# SparkFun_TMC6300_Breakout.net
KiCad netlist of a schematic drawn in EAGLE
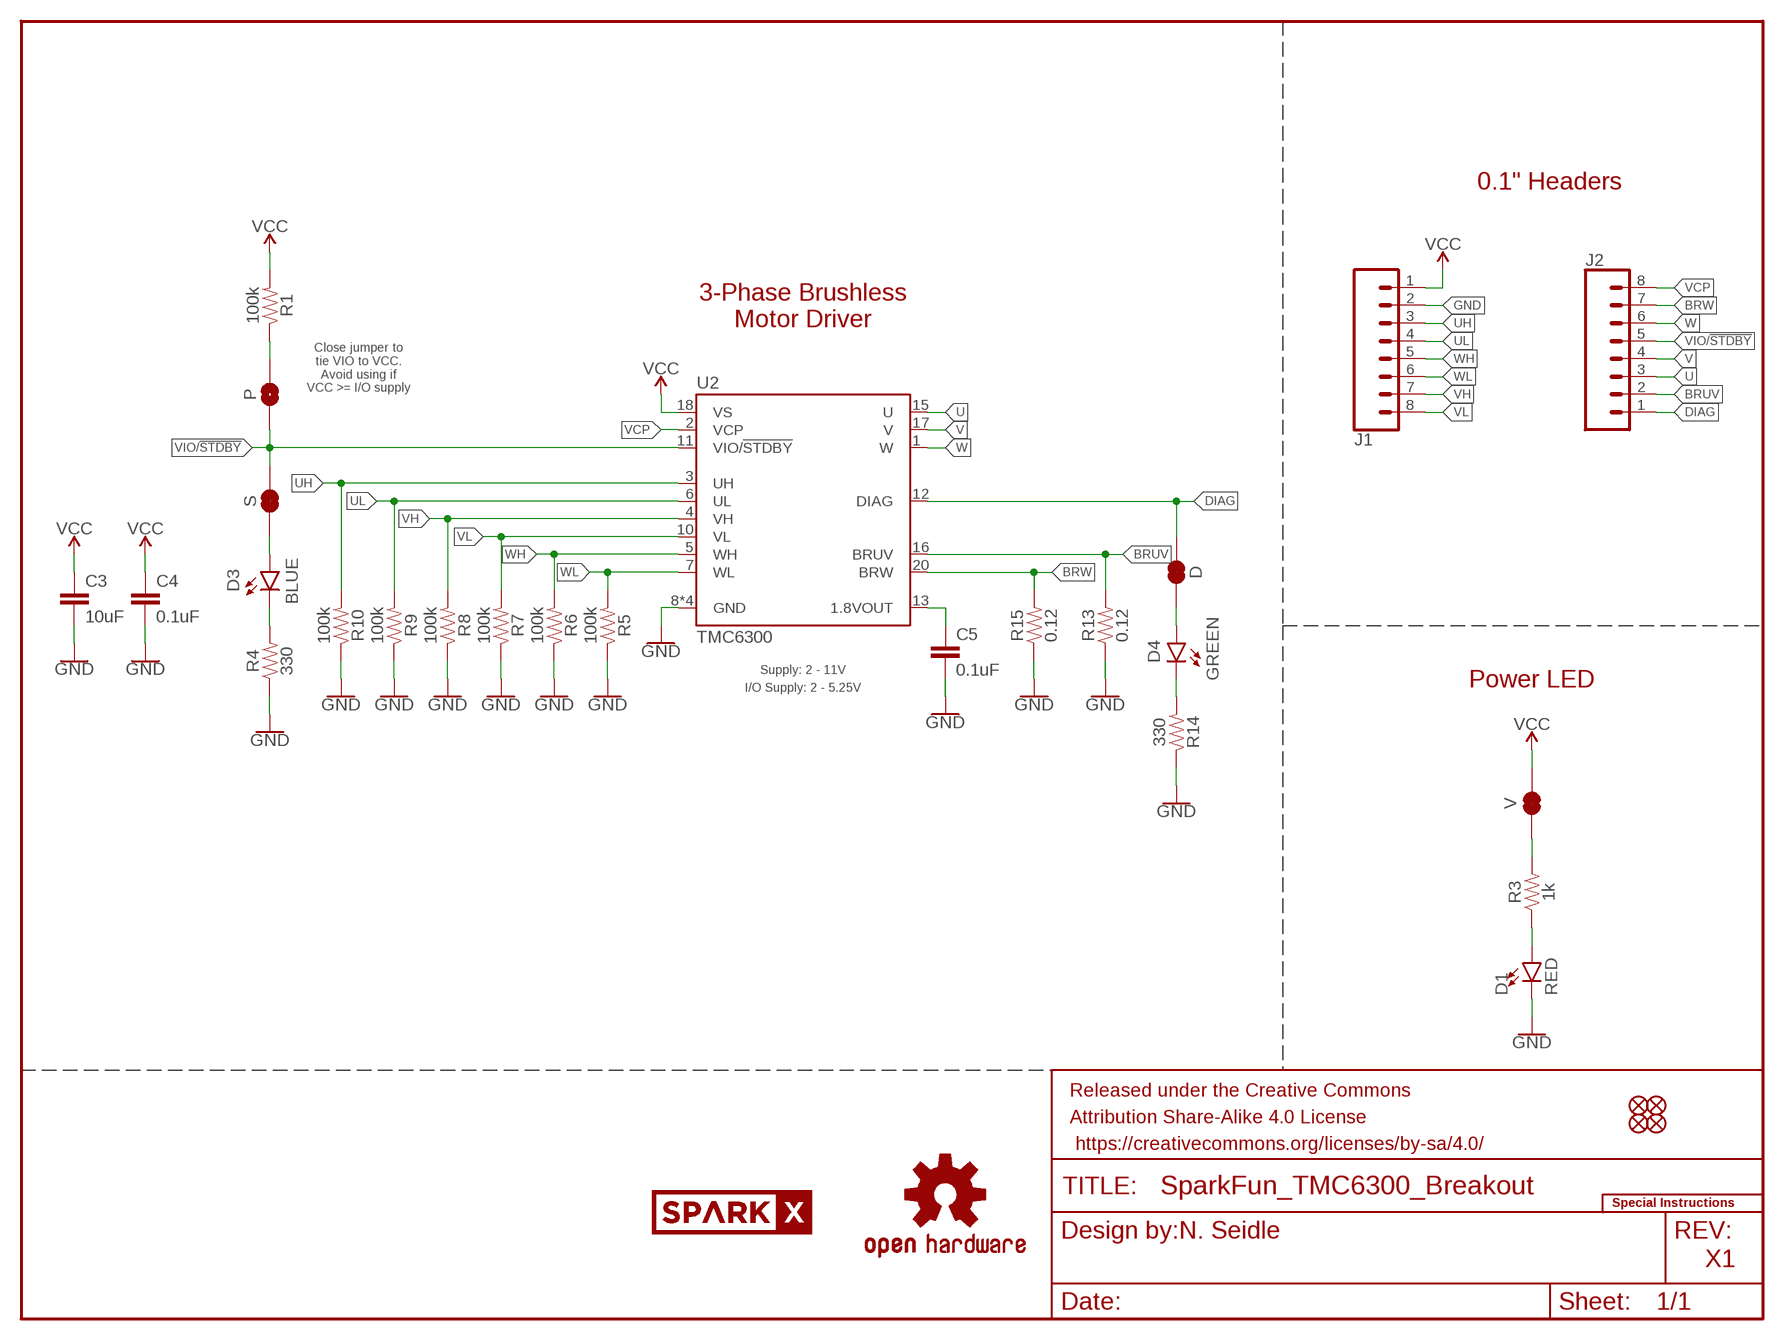
[diagram p0: schematic, sheet 1]

(export (version "E")
  (design (tool "Eeschema 10.0.6"))
  (components
    (comp (ref "C3")
      (value "10uF")
      (footprint "eagle-import:0805")
      (libsource (lib "eagle-import") (part "10UF-0805-25V-10%"))
    )
    (comp (ref "C4")
      (value "0.1uF")
      (footprint "eagle-import:0603")
      (libsource (lib "eagle-import") (part "0.1UF-0603-25V-10%-X7R-WE"))
    )
    (comp (ref "C5")
      (value "0.1uF")
      (footprint "eagle-import:0603")
      (libsource (lib "eagle-import") (part "0.1UF-0603-25V-10%-X7R-WE"))
    )
    (comp (ref "D")
      (value "JUMPER-SMT_2_NC_TRACE_SILK")
      (footprint "eagle-import:SMT-JUMPER_2_NC_TRACE_SILK")
      (libsource (lib "eagle-import") (part "JUMPER-SMT_2_NC_TRACE_SILK"))
    )
    (comp (ref "D1")
      (value "RED")
      (footprint "eagle-import:LED-0603")
      (libsource (lib "eagle-import") (part "LED-RED0603"))
    )
    (comp (ref "D3")
      (value "BLUE")
      (footprint "eagle-import:LED-0603")
      (libsource (lib "eagle-import") (part "LED-BLUE0603"))
    )
    (comp (ref "D4")
      (value "GREEN")
      (footprint "eagle-import:LED-0603")
      (libsource (lib "eagle-import") (part "LED-GREEN0603"))
    )
    (comp (ref "FD1")
      (value "FIDUCIALUFIDUCIAL")
      (footprint "eagle-import:FIDUCIAL-MICRO")
      (libsource (lib "eagle-import") (part "FIDUCIALUFIDUCIAL"))
    )
    (comp (ref "FD2")
      (value "FIDUCIALUFIDUCIAL")
      (footprint "eagle-import:FIDUCIAL-MICRO")
      (libsource (lib "eagle-import") (part "FIDUCIALUFIDUCIAL"))
    )
    (comp (ref "FD3")
      (value "FIDUCIALUFIDUCIAL")
      (footprint "eagle-import:FIDUCIAL-MICRO")
      (libsource (lib "eagle-import") (part "FIDUCIALUFIDUCIAL"))
    )
    (comp (ref "FD4")
      (value "FIDUCIALUFIDUCIAL")
      (footprint "eagle-import:FIDUCIAL-MICRO")
      (libsource (lib "eagle-import") (part "FIDUCIALUFIDUCIAL"))
    )
    (comp (ref "FRAME1")
      (value "FRAME-LETTER")
      (footprint "eagle-import:CREATIVE_COMMONS")
      (fields (field (name "DESIGNER") "Ricardo Ramos"))
      (libsource (lib "eagle-import") (part "FRAME-LETTER"))
    )
    (comp (ref "J1")
      (value "CONN_08LOCK_NO_SILK")
      (footprint "eagle-import:1X08_LOCK_NO_SILK")
      (libsource (lib "eagle-import") (part "CONN_08LOCK_NO_SILK"))
    )
    (comp (ref "J2")
      (value "CONN_08LOCK_NO_SILK")
      (footprint "eagle-import:1X08_LOCK_NO_SILK")
      (libsource (lib "eagle-import") (part "CONN_08LOCK_NO_SILK"))
    )
    (comp (ref "LOGO1")
      (value "OSHW-LOGONO_SILK")
      (footprint "eagle-import:DUMMY")
      (libsource (lib "eagle-import") (part "OSHW-LOGONO_SILK"))
    )
    (comp (ref "LOGO2")
      (value "SPECIAL_INSTRUCTIONS-ORDERING")
      (footprint "eagle-import:ORDERING_INSTRUCTIONS")
      (libsource (lib "eagle-import") (part "SPECIAL_INSTRUCTIONS-ORDERING"))
    )
    (comp (ref "P")
      (value "JUMPER-SMT_2_NO_SILK")
      (footprint "eagle-import:SMT-JUMPER_2_NO_SILK")
      (libsource (lib "eagle-import") (part "JUMPER-SMT_2_NO_SILK"))
    )
    (comp (ref "R1")
      (value "100k")
      (footprint "eagle-import:0603")
      (libsource (lib "eagle-import") (part "100KOHM-0603-1/10W-1%"))
    )
    (comp (ref "R3")
      (value "1k")
      (footprint "eagle-import:0603")
      (libsource (lib "eagle-import") (part "1KOHM-0603-1/10W-1%"))
    )
    (comp (ref "R4")
      (value "330")
      (footprint "eagle-import:0603")
      (libsource (lib "eagle-import") (part "330OHM-0603-1/10W-1%"))
    )
    (comp (ref "R5")
      (value "100k")
      (footprint "eagle-import:0603")
      (libsource (lib "eagle-import") (part "100KOHM-0603-1/10W-1%"))
    )
    (comp (ref "R6")
      (value "100k")
      (footprint "eagle-import:0603")
      (libsource (lib "eagle-import") (part "100KOHM-0603-1/10W-1%"))
    )
    (comp (ref "R7")
      (value "100k")
      (footprint "eagle-import:0603")
      (libsource (lib "eagle-import") (part "100KOHM-0603-1/10W-1%"))
    )
    (comp (ref "R8")
      (value "100k")
      (footprint "eagle-import:0603")
      (libsource (lib "eagle-import") (part "100KOHM-0603-1/10W-1%"))
    )
    (comp (ref "R9")
      (value "100k")
      (footprint "eagle-import:0603")
      (libsource (lib "eagle-import") (part "100KOHM-0603-1/10W-1%"))
    )
    (comp (ref "R10")
      (value "100k")
      (footprint "eagle-import:0603")
      (libsource (lib "eagle-import") (part "100KOHM-0603-1/10W-1%"))
    )
    (comp (ref "R13")
      (value "0.12")
      (footprint "eagle-import:1206")
      (libsource (lib "eagle-import") (part "0.12OHM-1206-1/2W-1%"))
    )
    (comp (ref "R14")
      (value "330")
      (footprint "eagle-import:0603")
      (libsource (lib "eagle-import") (part "330OHM-0603-1/10W-1%"))
    )
    (comp (ref "R15")
      (value "0.12")
      (footprint "eagle-import:1206")
      (libsource (lib "eagle-import") (part "0.12OHM-1206-1/2W-1%"))
    )
    (comp (ref "S")
      (value "JUMPER-SMT_2_NC_TRACE_SILK")
      (footprint "eagle-import:SMT-JUMPER_2_NC_TRACE_SILK")
      (libsource (lib "eagle-import") (part "JUMPER-SMT_2_NC_TRACE_SILK"))
    )
    (comp (ref "U$36")
      (value "SPARKX-LOGO2")
      (footprint "eagle-import:SPARKX-TINY")
      (libsource (lib "eagle-import") (part "SPARKX-LOGO2"))
    )
    (comp (ref "U$37")
      (value "SPARKX-LOGO2")
      (footprint "eagle-import:SPARKX-TINY")
      (libsource (lib "eagle-import") (part "SPARKX-LOGO2"))
    )
    (comp (ref "U2")
      (value "TMC6300")
      (footprint "eagle-import:QFN-20")
      (libsource (lib "eagle-import") (part "TMC6300"))
    )
    (comp (ref "V")
      (value "JUMPER-SMT_2_NC_TRACE_SILK")
      (footprint "eagle-import:SMT-JUMPER_2_NC_TRACE_SILK")
      (libsource (lib "eagle-import") (part "JUMPER-SMT_2_NC_TRACE_SILK"))
    )
  )
  (nets
    (net (code "1") (name "/VIO{slash}~{STDBY}") (class "Default")
      (node (ref "J2") (pin "5") (pinfunction "5_5") (pintype "passive"))
      (node (ref "P") (pin "1") (pinfunction "1_1") (pintype "passive"))
      (node (ref "S") (pin "2") (pinfunction "2_2") (pintype "passive"))
      (node (ref "U2") (pin "11") (pinfunction "VIO/~{STDBY}_11") (pintype "bidirectional"))
    )
    (net (code "2") (name "BRUV") (class "Default")
      (node (ref "J2") (pin "2") (pinfunction "2_2") (pintype "passive"))
      (node (ref "R13") (pin "2") (pinfunction "2_2") (pintype "passive"))
      (node (ref "U2") (pin "16") (pinfunction "BRUV_16") (pintype "bidirectional"))
    )
    (net (code "3") (name "BRW") (class "Default")
      (node (ref "J2") (pin "7") (pinfunction "7_7") (pintype "passive"))
      (node (ref "R15") (pin "2") (pinfunction "2_2") (pintype "passive"))
      (node (ref "U2") (pin "20") (pinfunction "BRW_20") (pintype "bidirectional"))
    )
    (net (code "4") (name "DIAG") (class "Default")
      (node (ref "D") (pin "2") (pinfunction "2_2") (pintype "passive"))
      (node (ref "J2") (pin "1") (pinfunction "1_1") (pintype "passive"))
      (node (ref "U2") (pin "12") (pinfunction "DIAG_12") (pintype "bidirectional"))
    )
    (net (code "5") (name "GND") (class "Default")
      (node (ref "C3") (pin "2") (pinfunction "2_2") (pintype "passive"))
      (node (ref "C4") (pin "2") (pinfunction "2_2") (pintype "passive"))
      (node (ref "C5") (pin "2") (pinfunction "2_2") (pintype "passive"))
      (node (ref "D1") (pin "C") (pinfunction "C_C") (pintype "passive"))
      (node (ref "J1") (pin "2") (pinfunction "2_2") (pintype "passive"))
      (node (ref "R10") (pin "1") (pinfunction "1_1") (pintype "passive"))
      (node (ref "R13") (pin "1") (pinfunction "1_1") (pintype "passive"))
      (node (ref "R14") (pin "1") (pinfunction "1_1") (pintype "passive"))
      (node (ref "R15") (pin "1") (pinfunction "1_1") (pintype "passive"))
      (node (ref "R4") (pin "1") (pinfunction "1_1") (pintype "passive"))
      (node (ref "R5") (pin "1") (pinfunction "1_1") (pintype "passive"))
      (node (ref "R6") (pin "1") (pinfunction "1_1") (pintype "passive"))
      (node (ref "R7") (pin "1") (pinfunction "1_1") (pintype "passive"))
      (node (ref "R8") (pin "1") (pinfunction "1_1") (pintype "passive"))
      (node (ref "R9") (pin "1") (pinfunction "1_1") (pintype "passive"))
      (node (ref "U2") (pin "14") (pinfunction "GND_14") (pintype "bidirectional"))
      (node (ref "U2") (pin "8") (pinfunction "GND_8") (pintype "bidirectional"))
      (node (ref "U2") (pin "9") (pinfunction "GND_9") (pintype "bidirectional"))
      (node (ref "U2") (pin "PAD") (pinfunction "GND_PAD") (pintype "bidirectional"))
    )
    (net (code "6") (name "Net-(D-Pad1)") (class "Default")
      (node (ref "D") (pin "1") (pinfunction "1_1") (pintype "passive"))
      (node (ref "D4") (pin "A") (pinfunction "A_A") (pintype "passive"))
    )
    (net (code "7") (name "Net-(D1-PadA)") (class "Default")
      (node (ref "D1") (pin "A") (pinfunction "A_A") (pintype "passive"))
      (node (ref "R3") (pin "1") (pinfunction "1_1") (pintype "passive"))
    )
    (net (code "8") (name "Net-(D3-PadA)") (class "Default")
      (node (ref "D3") (pin "A") (pinfunction "A_A") (pintype "passive"))
      (node (ref "S") (pin "1") (pinfunction "1_1") (pintype "passive"))
    )
    (net (code "9") (name "Net-(D3-PadC)") (class "Default")
      (node (ref "D3") (pin "C") (pinfunction "C_C") (pintype "passive"))
      (node (ref "R4") (pin "2") (pinfunction "2_2") (pintype "passive"))
    )
    (net (code "10") (name "Net-(D4-PadC)") (class "Default")
      (node (ref "D4") (pin "C") (pinfunction "C_C") (pintype "passive"))
      (node (ref "R14") (pin "2") (pinfunction "2_2") (pintype "passive"))
    )
    (net (code "11") (name "Net-(P-Pad2)") (class "Default")
      (node (ref "P") (pin "2") (pinfunction "2_2") (pintype "passive"))
      (node (ref "R1") (pin "1") (pinfunction "1_1") (pintype "passive"))
    )
    (net (code "12") (name "Net-(R3-Pad2)") (class "Default")
      (node (ref "R3") (pin "2") (pinfunction "2_2") (pintype "passive"))
      (node (ref "V") (pin "1") (pinfunction "1_1") (pintype "passive"))
    )
    (net (code "13") (name "Net-(U2-1.8VOUT)") (class "Default")
      (node (ref "C5") (pin "1") (pinfunction "1_1") (pintype "passive"))
      (node (ref "U2") (pin "13") (pinfunction "1.8VOUT_13") (pintype "bidirectional"))
    )
    (net (code "14") (name "U") (class "Default")
      (node (ref "J2") (pin "3") (pinfunction "3_3") (pintype "passive"))
      (node (ref "U2") (pin "15") (pinfunction "U_15") (pintype "bidirectional"))
    )
    (net (code "15") (name "UH") (class "Default")
      (node (ref "J1") (pin "3") (pinfunction "3_3") (pintype "passive"))
      (node (ref "R10") (pin "2") (pinfunction "2_2") (pintype "passive"))
      (node (ref "U2") (pin "3") (pinfunction "UH_3") (pintype "bidirectional"))
    )
    (net (code "16") (name "UL") (class "Default")
      (node (ref "J1") (pin "4") (pinfunction "4_4") (pintype "passive"))
      (node (ref "R9") (pin "2") (pinfunction "2_2") (pintype "passive"))
      (node (ref "U2") (pin "6") (pinfunction "UL_6") (pintype "bidirectional"))
    )
    (net (code "17") (name "V") (class "Default")
      (node (ref "J2") (pin "4") (pinfunction "4_4") (pintype "passive"))
      (node (ref "U2") (pin "17") (pinfunction "V_17") (pintype "bidirectional"))
    )
    (net (code "18") (name "VCC") (class "Default")
      (node (ref "C3") (pin "1") (pinfunction "1_1") (pintype "passive"))
      (node (ref "C4") (pin "1") (pinfunction "1_1") (pintype "passive"))
      (node (ref "J1") (pin "1") (pinfunction "1_1") (pintype "passive"))
      (node (ref "R1") (pin "2") (pinfunction "2_2") (pintype "passive"))
      (node (ref "U2") (pin "18") (pinfunction "VS_18") (pintype "bidirectional"))
      (node (ref "V") (pin "2") (pinfunction "2_2") (pintype "passive"))
    )
    (net (code "19") (name "VCP") (class "Default")
      (node (ref "J2") (pin "8") (pinfunction "8_8") (pintype "passive"))
      (node (ref "U2") (pin "2") (pinfunction "VCP_2") (pintype "bidirectional"))
    )
    (net (code "20") (name "VH") (class "Default")
      (node (ref "J1") (pin "7") (pinfunction "7_7") (pintype "passive"))
      (node (ref "R8") (pin "2") (pinfunction "2_2") (pintype "passive"))
      (node (ref "U2") (pin "4") (pinfunction "VH_4") (pintype "bidirectional"))
    )
    (net (code "21") (name "VL") (class "Default")
      (node (ref "J1") (pin "8") (pinfunction "8_8") (pintype "passive"))
      (node (ref "R7") (pin "2") (pinfunction "2_2") (pintype "passive"))
      (node (ref "U2") (pin "10") (pinfunction "VL_10") (pintype "bidirectional"))
    )
    (net (code "22") (name "W") (class "Default")
      (node (ref "J2") (pin "6") (pinfunction "6_6") (pintype "passive"))
      (node (ref "U2") (pin "1") (pinfunction "W_1") (pintype "bidirectional"))
    )
    (net (code "23") (name "WH") (class "Default")
      (node (ref "J1") (pin "5") (pinfunction "5_5") (pintype "passive"))
      (node (ref "R6") (pin "2") (pinfunction "2_2") (pintype "passive"))
      (node (ref "U2") (pin "5") (pinfunction "WH_5") (pintype "bidirectional"))
    )
    (net (code "24") (name "WL") (class "Default")
      (node (ref "J1") (pin "6") (pinfunction "6_6") (pintype "passive"))
      (node (ref "R5") (pin "2") (pinfunction "2_2") (pintype "passive"))
      (node (ref "U2") (pin "7") (pinfunction "WL_7") (pintype "bidirectional"))
    )
  )
)
